# ESP32_JTAG_Schematic.net
KiCad netlist of a schematic drawn in EasyEDA
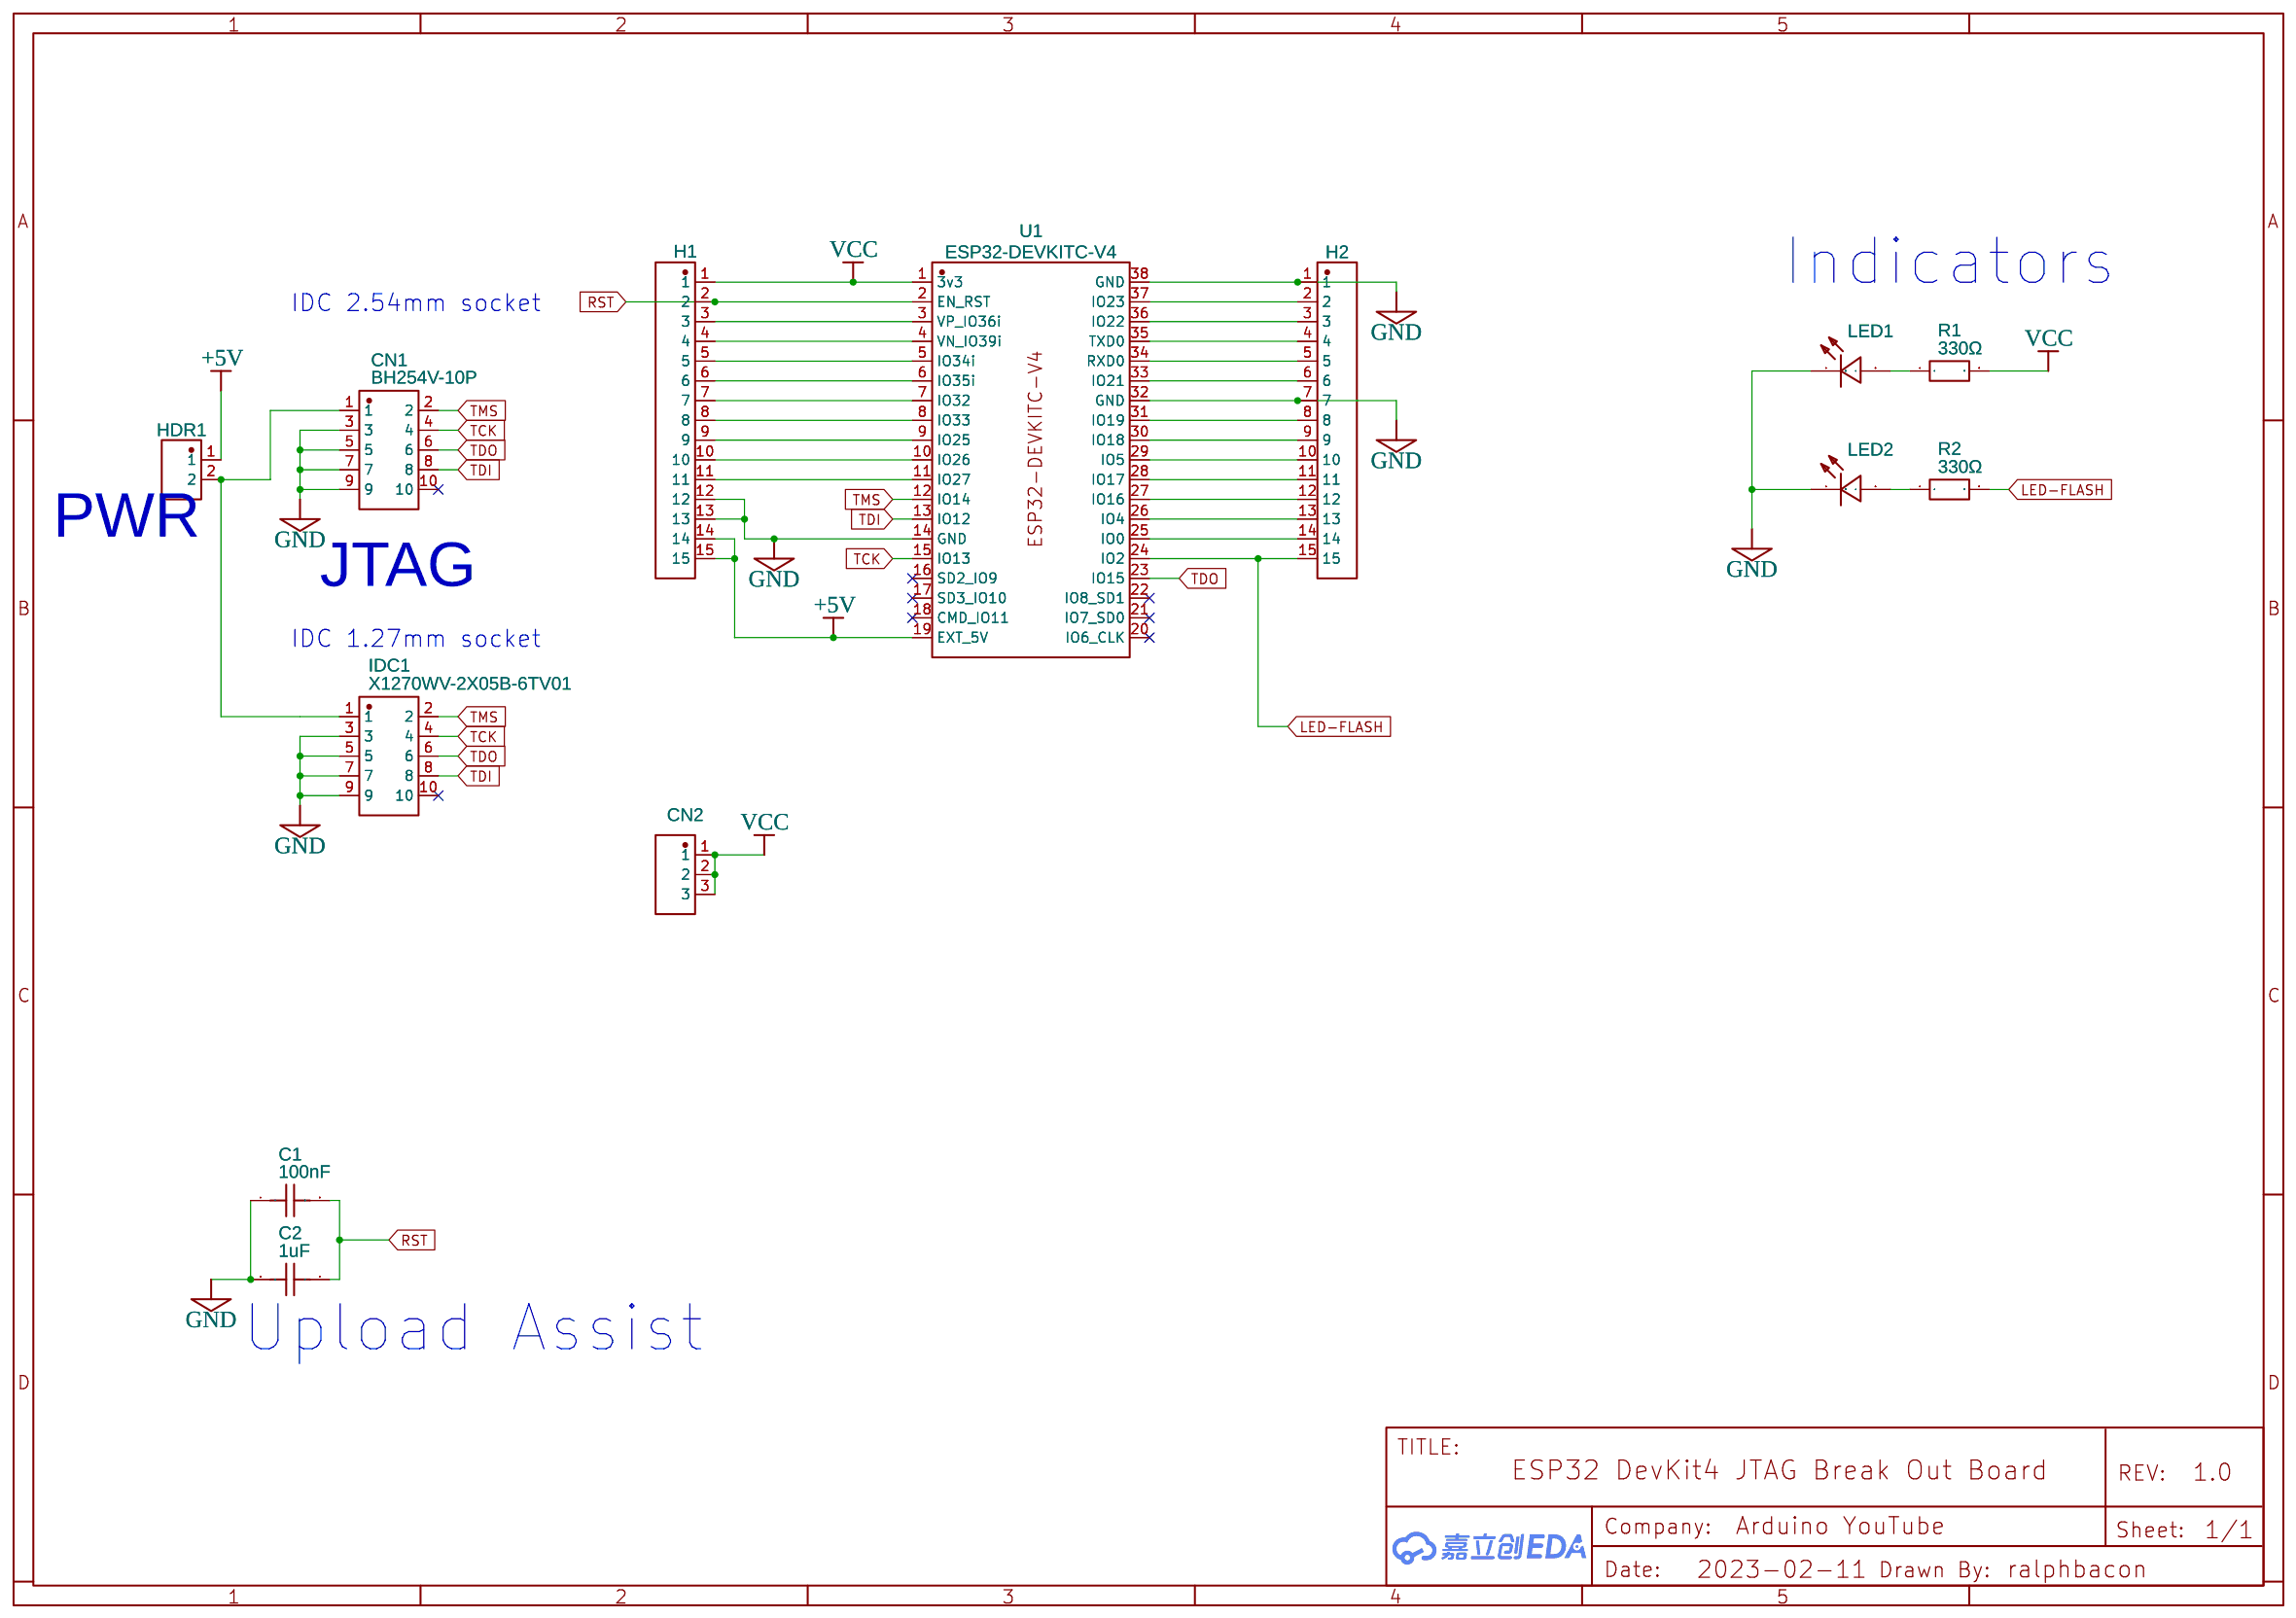
[diagram p0: schematic sheet]

(export (version "E")
  (design (tool "Eeschema 10.0.6"))
  (components
    (comp (ref "C1")
      (value "100nF")
      (fields
        (field (name "BOM_Manufacturer Part") "0805ZC104KAT2A")
        (field (name "BOM_Supplier Part") "C597440")
      )
      (libsource (lib "") (part "0805ZC104KAT2A"))
    )
    (comp (ref "C2")
      (value "1uF")
      (fields
        (field (name "BOM_Manufacturer Part") "TCC0805X7R105K500FTA")
        (field (name "BOM_Supplier Part") "C282737")
      )
      (libsource (lib "") (part "TCC0805X7R105K500FTA"))
    )
    (comp (ref "CN1")
      (value "BH254V-10P")
      (fields (field (name "BOM_Supplier Part") "C492442"))
      (libsource (lib "") (part "BH254V-10P"))
    )
    (comp (ref "CN2")
      (value "G800W305018EU")
      (fields (field (name "BOM_Supplier Part") "C9900019508"))
      (libsource (lib "") (part "G800W305018EU"))
    )
    (comp (ref "H1")
      (value "PZ254-1-15-Z-8.5")
      (fields (field (name "BOM_Supplier Part") "C2894938"))
      (libsource (lib "") (part "PZ254-1-15-Z-8.5_1"))
    )
    (comp (ref "H2")
      (value "PZ254-1-15-Z-8.5")
      (fields (field (name "BOM_Supplier Part") "C2894938"))
      (libsource (lib "") (part "PZ254-1-15-Z-8.5"))
    )
    (comp (ref "HDR1")
      (value "SIP2-2.54MM2X1双排针")
      (fields
        (field (name "BOM_Manufacturer Part") "SIP2-2.54mm2X1双排针")
        (field (name "BOM_Supplier Part") "C9900003704")
      )
      (libsource (lib "") (part "SIP2-2.54MM2X1双排针"))
    )
    (comp (ref "IDC1")
      (value "X1270WV-2X05B-6TV01")
      (fields
        (field (name "BOM_Manufacturer Part") "X1270WV-2x05B-6TV01")
        (field (name "BOM_Supplier Part") "C2962225")
      )
      (libsource (lib "") (part "X1270WV-2X05B-6TV01"))
    )
    (comp (ref "LED1")
      (value "SMDREDLED红色超高亮0805")
      (fields
        (field (name "BOM_Manufacturer Part") "SMDRedLED红色超高亮0805")
        (field (name "BOM_Supplier Part") "C9900019100")
      )
      (libsource (lib "") (part "SMDREDLED红色超高亮0805"))
    )
    (comp (ref "LED2")
      (value "SMDREDLED红色超高亮0805")
      (fields
        (field (name "BOM_Manufacturer Part") "SMDRedLED红色超高亮0805")
        (field (name "BOM_Supplier Part") "C9900019100")
      )
      (libsource (lib "") (part "SMDREDLED红色超高亮0805"))
    )
    (comp (ref "R1")
      (value "330Ω")
      (fields
        (field (name "BOM_Manufacturer Part") "RT0603DRD07330RL")
        (field (name "BOM_Supplier Part") "C723588")
      )
      (libsource (lib "") (part "RT0603DRD07330RL"))
    )
    (comp (ref "R2")
      (value "330Ω")
      (fields
        (field (name "BOM_Manufacturer Part") "RT0603DRD07330RL")
        (field (name "BOM_Supplier Part") "C723588")
      )
      (libsource (lib "") (part "RT0603DRD07330RL"))
    )
    (comp (ref "U1") (value "ESP32-DEVKITC-V4") (libsource (lib "") (part "ESP32-DevKitC v4")))
  )
  (nets
    (net (code "1") (name "+5V") (class "Default")
      (node (ref "H1") (pin "14") (pinfunction "14_14") (pintype "unspecified"))
      (node (ref "H1") (pin "15") (pinfunction "15_15") (pintype "unspecified"))
      (node (ref "HDR1") (pin "1") (pinfunction "1_1") (pintype "unspecified"))
      (node (ref "U1") (pin "19") (pinfunction "EXT_5V_19") (pintype "unspecified"))
    )
    (net (code "2") (name "GND") (class "Default")
      (node (ref "C1") (pin "1") (pinfunction "1_1") (pintype "unspecified"))
      (node (ref "C2") (pin "2") (pinfunction "2_2") (pintype "unspecified"))
      (node (ref "CN1") (pin "3") (pinfunction "3_3") (pintype "unspecified"))
      (node (ref "CN1") (pin "5") (pinfunction "5_5") (pintype "unspecified"))
      (node (ref "CN1") (pin "7") (pinfunction "7_7") (pintype "unspecified"))
      (node (ref "CN1") (pin "9") (pinfunction "9_9") (pintype "unspecified"))
      (node (ref "H1") (pin "12") (pinfunction "12_12") (pintype "unspecified"))
      (node (ref "H1") (pin "13") (pinfunction "13_13") (pintype "unspecified"))
      (node (ref "H2") (pin "1") (pinfunction "1_1") (pintype "unspecified"))
      (node (ref "H2") (pin "7") (pinfunction "7_7") (pintype "unspecified"))
      (node (ref "IDC1") (pin "3") (pinfunction "3_3") (pintype "unspecified"))
      (node (ref "IDC1") (pin "5") (pinfunction "5_5") (pintype "unspecified"))
      (node (ref "IDC1") (pin "7") (pinfunction "7_7") (pintype "unspecified"))
      (node (ref "IDC1") (pin "9") (pinfunction "9_9") (pintype "unspecified"))
      (node (ref "LED1") (pin "1") (pinfunction "C_1") (pintype "unspecified"))
      (node (ref "LED2") (pin "1") (pinfunction "C_1") (pintype "unspecified"))
      (node (ref "U1") (pin "14") (pinfunction "GND_14") (pintype "unspecified"))
      (node (ref "U1") (pin "32") (pinfunction "GND_32") (pintype "unspecified"))
      (node (ref "U1") (pin "38") (pinfunction "GND_38") (pintype "unspecified"))
    )
    (net (code "3") (name "LED-FLASH") (class "Default")
      (node (ref "H2") (pin "15") (pinfunction "15_15") (pintype "unspecified"))
      (node (ref "R2") (pin "2") (pinfunction "2_2") (pintype "unspecified"))
      (node (ref "U1") (pin "24") (pinfunction "IO2_24") (pintype "unspecified"))
    )
    (net (code "4") (name "Net-(CN1-Pad1)") (class "Default")
      (node (ref "CN1") (pin "1") (pinfunction "1_1") (pintype "unspecified"))
      (node (ref "HDR1") (pin "2") (pinfunction "2_2") (pintype "unspecified"))
      (node (ref "IDC1") (pin "1") (pinfunction "1_1") (pintype "unspecified"))
    )
    (net (code "5") (name "Net-(LED1-A)") (class "Default")
      (node (ref "LED1") (pin "2") (pinfunction "A_2") (pintype "unspecified"))
      (node (ref "R1") (pin "1") (pinfunction "1_1") (pintype "unspecified"))
    )
    (net (code "6") (name "Net-(LED2-A)") (class "Default")
      (node (ref "LED2") (pin "2") (pinfunction "A_2") (pintype "unspecified"))
      (node (ref "R2") (pin "1") (pinfunction "1_1") (pintype "unspecified"))
    )
    (net (code "7") (name "Net-(U1-IO0)") (class "Default")
      (node (ref "H2") (pin "14") (pinfunction "14_14") (pintype "unspecified"))
      (node (ref "U1") (pin "25") (pinfunction "IO0_25") (pintype "unspecified"))
    )
    (net (code "8") (name "Net-(U1-IO4)") (class "Default")
      (node (ref "H2") (pin "13") (pinfunction "13_13") (pintype "unspecified"))
      (node (ref "U1") (pin "26") (pinfunction "IO4_26") (pintype "unspecified"))
    )
    (net (code "9") (name "Net-(U1-IO5)") (class "Default")
      (node (ref "H2") (pin "10") (pinfunction "10_10") (pintype "unspecified"))
      (node (ref "U1") (pin "29") (pinfunction "IO5_29") (pintype "unspecified"))
    )
    (net (code "10") (name "Net-(U1-IO16)") (class "Default")
      (node (ref "H2") (pin "12") (pinfunction "12_12") (pintype "unspecified"))
      (node (ref "U1") (pin "27") (pinfunction "IO16_27") (pintype "unspecified"))
    )
    (net (code "11") (name "Net-(U1-IO17)") (class "Default")
      (node (ref "H2") (pin "11") (pinfunction "11_11") (pintype "unspecified"))
      (node (ref "U1") (pin "28") (pinfunction "IO17_28") (pintype "unspecified"))
    )
    (net (code "12") (name "Net-(U1-IO18)") (class "Default")
      (node (ref "H2") (pin "9") (pinfunction "9_9") (pintype "unspecified"))
      (node (ref "U1") (pin "30") (pinfunction "IO18_30") (pintype "unspecified"))
    )
    (net (code "13") (name "Net-(U1-IO19)") (class "Default")
      (node (ref "H2") (pin "8") (pinfunction "8_8") (pintype "unspecified"))
      (node (ref "U1") (pin "31") (pinfunction "IO19_31") (pintype "unspecified"))
    )
    (net (code "14") (name "Net-(U1-IO21)") (class "Default")
      (node (ref "H2") (pin "6") (pinfunction "6_6") (pintype "unspecified"))
      (node (ref "U1") (pin "33") (pinfunction "IO21_33") (pintype "unspecified"))
    )
    (net (code "15") (name "Net-(U1-IO22)") (class "Default")
      (node (ref "H2") (pin "3") (pinfunction "3_3") (pintype "unspecified"))
      (node (ref "U1") (pin "36") (pinfunction "IO22_36") (pintype "unspecified"))
    )
    (net (code "16") (name "Net-(U1-IO23)") (class "Default")
      (node (ref "H2") (pin "2") (pinfunction "2_2") (pintype "unspecified"))
      (node (ref "U1") (pin "37") (pinfunction "IO23_37") (pintype "unspecified"))
    )
    (net (code "17") (name "Net-(U1-IO25)") (class "Default")
      (node (ref "H1") (pin "9") (pinfunction "9_9") (pintype "unspecified"))
      (node (ref "U1") (pin "9") (pinfunction "IO25_9") (pintype "unspecified"))
    )
    (net (code "18") (name "Net-(U1-IO26)") (class "Default")
      (node (ref "H1") (pin "10") (pinfunction "10_10") (pintype "unspecified"))
      (node (ref "U1") (pin "10") (pinfunction "IO26_10") (pintype "unspecified"))
    )
    (net (code "19") (name "Net-(U1-IO27)") (class "Default")
      (node (ref "H1") (pin "11") (pinfunction "11_11") (pintype "unspecified"))
      (node (ref "U1") (pin "11") (pinfunction "IO27_11") (pintype "unspecified"))
    )
    (net (code "20") (name "Net-(U1-IO32)") (class "Default")
      (node (ref "H1") (pin "7") (pinfunction "7_7") (pintype "unspecified"))
      (node (ref "U1") (pin "7") (pinfunction "IO32_7") (pintype "unspecified"))
    )
    (net (code "21") (name "Net-(U1-IO33)") (class "Default")
      (node (ref "H1") (pin "8") (pinfunction "8_8") (pintype "unspecified"))
      (node (ref "U1") (pin "8") (pinfunction "IO33_8") (pintype "unspecified"))
    )
    (net (code "22") (name "Net-(U1-IO34i)") (class "Default")
      (node (ref "H1") (pin "5") (pinfunction "5_5") (pintype "unspecified"))
      (node (ref "U1") (pin "5") (pinfunction "IO34i_5") (pintype "unspecified"))
    )
    (net (code "23") (name "Net-(U1-IO35i)") (class "Default")
      (node (ref "H1") (pin "6") (pinfunction "6_6") (pintype "unspecified"))
      (node (ref "U1") (pin "6") (pinfunction "IO35i_6") (pintype "unspecified"))
    )
    (net (code "24") (name "Net-(U1-RXD0)") (class "Default")
      (node (ref "H2") (pin "5") (pinfunction "5_5") (pintype "unspecified"))
      (node (ref "U1") (pin "34") (pinfunction "RXD0_34") (pintype "unspecified"))
    )
    (net (code "25") (name "Net-(U1-TXD0)") (class "Default")
      (node (ref "H2") (pin "4") (pinfunction "4_4") (pintype "unspecified"))
      (node (ref "U1") (pin "35") (pinfunction "TXD0_35") (pintype "unspecified"))
    )
    (net (code "26") (name "Net-(U1-VN_IO39i)") (class "Default")
      (node (ref "H1") (pin "4") (pinfunction "4_4") (pintype "unspecified"))
      (node (ref "U1") (pin "4") (pinfunction "VN_IO39i_4") (pintype "unspecified"))
    )
    (net (code "27") (name "Net-(U1-VP_IO36i)") (class "Default")
      (node (ref "H1") (pin "3") (pinfunction "3_3") (pintype "unspecified"))
      (node (ref "U1") (pin "3") (pinfunction "VP_IO36i_3") (pintype "unspecified"))
    )
    (net (code "28") (name "RST") (class "Default")
      (node (ref "C1") (pin "2") (pinfunction "2_2") (pintype "unspecified"))
      (node (ref "C2") (pin "1") (pinfunction "1_1") (pintype "unspecified"))
      (node (ref "H1") (pin "2") (pinfunction "2_2") (pintype "unspecified"))
      (node (ref "U1") (pin "2") (pinfunction "EN_RST_2") (pintype "unspecified"))
    )
    (net (code "29") (name "TCK") (class "Default")
      (node (ref "CN1") (pin "4") (pinfunction "4_4") (pintype "unspecified"))
      (node (ref "IDC1") (pin "4") (pinfunction "4_4") (pintype "unspecified"))
      (node (ref "U1") (pin "15") (pinfunction "IO13_15") (pintype "unspecified"))
    )
    (net (code "30") (name "TDI") (class "Default")
      (node (ref "CN1") (pin "8") (pinfunction "8_8") (pintype "unspecified"))
      (node (ref "IDC1") (pin "8") (pinfunction "8_8") (pintype "unspecified"))
      (node (ref "U1") (pin "13") (pinfunction "IO12_13") (pintype "unspecified"))
    )
    (net (code "31") (name "TDO") (class "Default")
      (node (ref "CN1") (pin "6") (pinfunction "6_6") (pintype "unspecified"))
      (node (ref "IDC1") (pin "6") (pinfunction "6_6") (pintype "unspecified"))
      (node (ref "U1") (pin "23") (pinfunction "IO15_23") (pintype "unspecified"))
    )
    (net (code "32") (name "TMS") (class "Default")
      (node (ref "CN1") (pin "2") (pinfunction "2_2") (pintype "unspecified"))
      (node (ref "IDC1") (pin "2") (pinfunction "2_2") (pintype "unspecified"))
      (node (ref "U1") (pin "12") (pinfunction "IO14_12") (pintype "unspecified"))
    )
    (net (code "33") (name "VCC") (class "Default")
      (node (ref "CN2") (pin "1") (pinfunction "1_1") (pintype "unspecified"))
      (node (ref "CN2") (pin "2") (pinfunction "2_2") (pintype "unspecified"))
      (node (ref "CN2") (pin "3") (pinfunction "3_3") (pintype "unspecified"))
      (node (ref "H1") (pin "1") (pinfunction "1_1") (pintype "unspecified"))
      (node (ref "R1") (pin "2") (pinfunction "2_2") (pintype "unspecified"))
      (node (ref "U1") (pin "1") (pinfunction "3v3_1") (pintype "unspecified"))
    )
    (net (code "34") (name "unconnected-(CN1-Pad10)") (class "Default")
      (node (ref "CN1") (pin "10") (pinfunction "10_10") (pintype "unspecified+no_connect"))
    )
    (net (code "35") (name "unconnected-(IDC1-Pad10)") (class "Default")
      (node (ref "IDC1") (pin "10") (pinfunction "10_10") (pintype "unspecified+no_connect"))
    )
    (net (code "36") (name "unconnected-(U1-CMD_IO11-Pad18)") (class "Default")
      (node (ref "U1") (pin "18") (pinfunction "CMD_IO11_18") (pintype "unspecified+no_connect"))
    )
    (net (code "37") (name "unconnected-(U1-IO6_CLK-Pad20)") (class "Default")
      (node (ref "U1") (pin "20") (pinfunction "IO6_CLK_20") (pintype "unspecified+no_connect"))
    )
    (net (code "38") (name "unconnected-(U1-IO7_SD0-Pad21)") (class "Default")
      (node (ref "U1") (pin "21") (pinfunction "IO7_SD0_21") (pintype "unspecified+no_connect"))
    )
    (net (code "39") (name "unconnected-(U1-IO8_SD1-Pad22)") (class "Default")
      (node (ref "U1") (pin "22") (pinfunction "IO8_SD1_22") (pintype "unspecified+no_connect"))
    )
    (net (code "40") (name "unconnected-(U1-SD2_IO9-Pad16)") (class "Default")
      (node (ref "U1") (pin "16") (pinfunction "SD2_IO9_16") (pintype "unspecified+no_connect"))
    )
    (net (code "41") (name "unconnected-(U1-SD3_IO10-Pad17)") (class "Default")
      (node (ref "U1") (pin "17") (pinfunction "SD3_IO10_17") (pintype "unspecified+no_connect"))
    )
  )
)
